# bierkasten.net
KiCad netlist of a schematic drawn in EAGLE
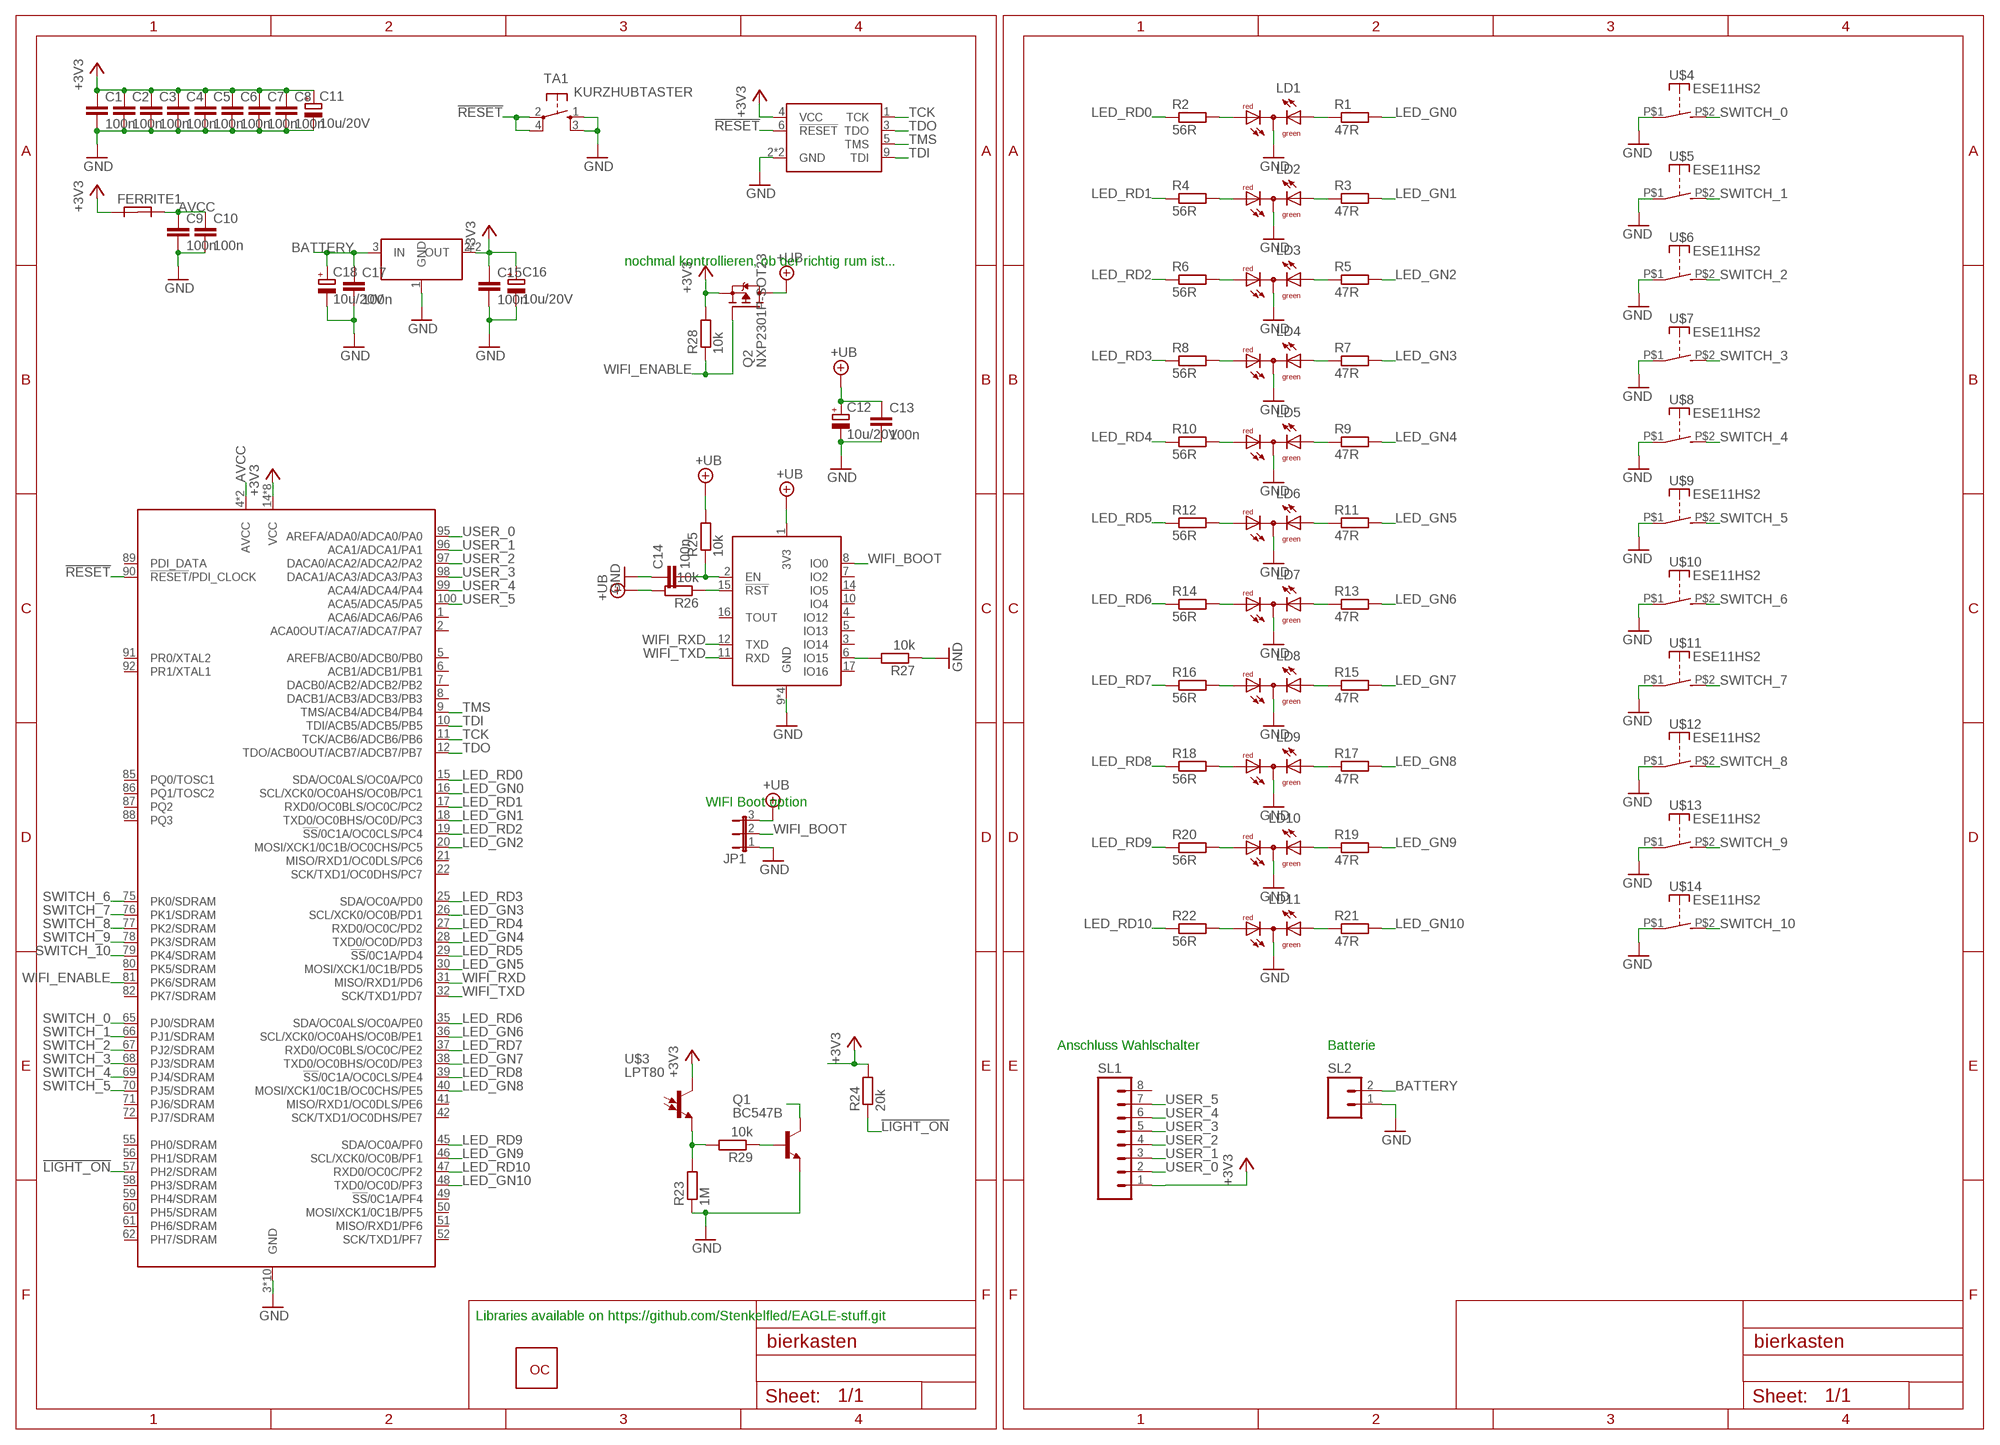
[diagram p0: schematic, sheet 1]

(export (version "E")
  (design (tool "Eeschema 10.0.6"))
  (components
    (comp (ref "C1")
      (value "100n")
      (footprint "eagle-import:C0603")
      (libsource (lib "eagle-import") (part "C-EUC0603"))
    )
    (comp (ref "C2")
      (value "100n")
      (footprint "eagle-import:C0603")
      (libsource (lib "eagle-import") (part "C-EUC0603"))
    )
    (comp (ref "C3")
      (value "100n")
      (footprint "eagle-import:C0603")
      (libsource (lib "eagle-import") (part "C-EUC0603"))
    )
    (comp (ref "C4")
      (value "100n")
      (footprint "eagle-import:C0603")
      (libsource (lib "eagle-import") (part "C-EUC0603"))
    )
    (comp (ref "C5")
      (value "100n")
      (footprint "eagle-import:C0603")
      (libsource (lib "eagle-import") (part "C-EUC0603"))
    )
    (comp (ref "C6")
      (value "100n")
      (footprint "eagle-import:C0603")
      (libsource (lib "eagle-import") (part "C-EUC0603"))
    )
    (comp (ref "C7")
      (value "100n")
      (footprint "eagle-import:C0603")
      (libsource (lib "eagle-import") (part "C-EUC0603"))
    )
    (comp (ref "C8")
      (value "100n")
      (footprint "eagle-import:C0603")
      (libsource (lib "eagle-import") (part "C-EUC0603"))
    )
    (comp (ref "C9")
      (value "100n")
      (footprint "eagle-import:C0603")
      (libsource (lib "eagle-import") (part "C-EUC0603"))
    )
    (comp (ref "C10")
      (value "100n")
      (footprint "eagle-import:C0603")
      (libsource (lib "eagle-import") (part "C-EUC0603"))
    )
    (comp (ref "C11")
      (value "10u/20V")
      (footprint "eagle-import:B_3528-21W")
      (libsource (lib "eagle-import") (part "CPOL-EUB/3528-21W"))
    )
    (comp (ref "C12")
      (value "10u/20V")
      (footprint "eagle-import:B_3528-21W")
      (libsource (lib "eagle-import") (part "CPOL-EUB/3528-21W"))
    )
    (comp (ref "C13")
      (value "100n")
      (footprint "eagle-import:C0603")
      (libsource (lib "eagle-import") (part "C-EUC0603"))
    )
    (comp (ref "C14")
      (value "100n")
      (footprint "eagle-import:C0603")
      (libsource (lib "eagle-import") (part "C-EUC0603"))
    )
    (comp (ref "C15")
      (value "100n")
      (footprint "eagle-import:C0603")
      (libsource (lib "eagle-import") (part "C-EUC0603"))
    )
    (comp (ref "C16")
      (value "10u/20V")
      (footprint "eagle-import:B_3528-21W")
      (libsource (lib "eagle-import") (part "CPOL-EUB/3528-21W"))
    )
    (comp (ref "C17")
      (value "100n")
      (footprint "eagle-import:C0603")
      (libsource (lib "eagle-import") (part "C-EUC0603"))
    )
    (comp (ref "C18")
      (value "10u/20V")
      (footprint "eagle-import:B_3528-21W")
      (libsource (lib "eagle-import") (part "CPOL-EUB/3528-21W"))
    )
    (comp (ref "FERRITE1")
      (value "FERRITE-EU_0805")
      (footprint "eagle-import:L0805")
      (libsource (lib "eagle-import") (part "FERRITE-EU_0805"))
    )
    (comp (ref "JP1")
      (value "JP2E")
      (footprint "eagle-import:JP2")
      (libsource (lib "eagle-import") (part "JP2E"))
    )
    (comp (ref "LD1")
      (value "DUOLED-RG-C-WIRE")
      (footprint "eagle-import:DUOLED-C-WIRE")
      (libsource (lib "eagle-import") (part "DUOLED-RG-C-WIRE"))
    )
    (comp (ref "LD2")
      (value "DUOLED-RG-C-WIRE")
      (footprint "eagle-import:DUOLED-C-WIRE")
      (libsource (lib "eagle-import") (part "DUOLED-RG-C-WIRE"))
    )
    (comp (ref "LD3")
      (value "DUOLED-RG-C-WIRE")
      (footprint "eagle-import:DUOLED-C-WIRE")
      (libsource (lib "eagle-import") (part "DUOLED-RG-C-WIRE"))
    )
    (comp (ref "LD4")
      (value "DUOLED-RG-C-WIRE")
      (footprint "eagle-import:DUOLED-C-WIRE")
      (libsource (lib "eagle-import") (part "DUOLED-RG-C-WIRE"))
    )
    (comp (ref "LD5")
      (value "DUOLED-RG-C-WIRE")
      (footprint "eagle-import:DUOLED-C-WIRE")
      (libsource (lib "eagle-import") (part "DUOLED-RG-C-WIRE"))
    )
    (comp (ref "LD6")
      (value "DUOLED-RG-C-WIRE")
      (footprint "eagle-import:DUOLED-C-WIRE")
      (libsource (lib "eagle-import") (part "DUOLED-RG-C-WIRE"))
    )
    (comp (ref "LD7")
      (value "DUOLED-RG-C-WIRE")
      (footprint "eagle-import:DUOLED-C-WIRE")
      (libsource (lib "eagle-import") (part "DUOLED-RG-C-WIRE"))
    )
    (comp (ref "LD8")
      (value "DUOLED-RG-C-WIRE")
      (footprint "eagle-import:DUOLED-C-WIRE")
      (libsource (lib "eagle-import") (part "DUOLED-RG-C-WIRE"))
    )
    (comp (ref "LD9")
      (value "DUOLED-RG-C-WIRE")
      (footprint "eagle-import:DUOLED-C-WIRE")
      (libsource (lib "eagle-import") (part "DUOLED-RG-C-WIRE"))
    )
    (comp (ref "LD10")
      (value "DUOLED-RG-C-WIRE")
      (footprint "eagle-import:DUOLED-C-WIRE")
      (libsource (lib "eagle-import") (part "DUOLED-RG-C-WIRE"))
    )
    (comp (ref "LD11")
      (value "DUOLED-RG-C-WIRE")
      (footprint "eagle-import:DUOLED-C-WIRE")
      (libsource (lib "eagle-import") (part "DUOLED-RG-C-WIRE"))
    )
    (comp (ref "Q1")
      (value "BC547B")
      (footprint "eagle-import:TO92")
      (libsource (lib "eagle-import") (part "BC547B"))
    )
    (comp (ref "Q2")
      (value "NXP2301P-SOT23")
      (footprint "eagle-import:SOT23")
      (libsource (lib "eagle-import") (part "NXP2301P-SOT23"))
    )
    (comp (ref "R1")
      (value "47R")
      (footprint "eagle-import:R0603")
      (libsource (lib "eagle-import") (part "rcl_STE_R-EU_R0603"))
    )
    (comp (ref "R2")
      (value "56R")
      (footprint "eagle-import:R0603")
      (libsource (lib "eagle-import") (part "rcl_STE_R-EU_R0603"))
    )
    (comp (ref "R3")
      (value "47R")
      (footprint "eagle-import:R0603")
      (libsource (lib "eagle-import") (part "rcl_STE_R-EU_R0603"))
    )
    (comp (ref "R4")
      (value "56R")
      (footprint "eagle-import:R0603")
      (libsource (lib "eagle-import") (part "rcl_STE_R-EU_R0603"))
    )
    (comp (ref "R5")
      (value "47R")
      (footprint "eagle-import:R0603")
      (libsource (lib "eagle-import") (part "rcl_STE_R-EU_R0603"))
    )
    (comp (ref "R6")
      (value "56R")
      (footprint "eagle-import:R0603")
      (libsource (lib "eagle-import") (part "rcl_STE_R-EU_R0603"))
    )
    (comp (ref "R7")
      (value "47R")
      (footprint "eagle-import:R0603")
      (libsource (lib "eagle-import") (part "rcl_STE_R-EU_R0603"))
    )
    (comp (ref "R8")
      (value "56R")
      (footprint "eagle-import:R0603")
      (libsource (lib "eagle-import") (part "rcl_STE_R-EU_R0603"))
    )
    (comp (ref "R9")
      (value "47R")
      (footprint "eagle-import:R0603")
      (libsource (lib "eagle-import") (part "rcl_STE_R-EU_R0603"))
    )
    (comp (ref "R10")
      (value "56R")
      (footprint "eagle-import:R0603")
      (libsource (lib "eagle-import") (part "rcl_STE_R-EU_R0603"))
    )
    (comp (ref "R11")
      (value "47R")
      (footprint "eagle-import:R0603")
      (libsource (lib "eagle-import") (part "rcl_STE_R-EU_R0603"))
    )
    (comp (ref "R12")
      (value "56R")
      (footprint "eagle-import:R0603")
      (libsource (lib "eagle-import") (part "rcl_STE_R-EU_R0603"))
    )
    (comp (ref "R13")
      (value "47R")
      (footprint "eagle-import:R0603")
      (libsource (lib "eagle-import") (part "rcl_STE_R-EU_R0603"))
    )
    (comp (ref "R14")
      (value "56R")
      (footprint "eagle-import:R0603")
      (libsource (lib "eagle-import") (part "rcl_STE_R-EU_R0603"))
    )
    (comp (ref "R15")
      (value "47R")
      (footprint "eagle-import:R0603")
      (libsource (lib "eagle-import") (part "R-EU_R0603"))
    )
    (comp (ref "R16")
      (value "56R")
      (footprint "eagle-import:R0603")
      (libsource (lib "eagle-import") (part "rcl_STE_R-EU_R0603"))
    )
    (comp (ref "R17")
      (value "47R")
      (footprint "eagle-import:R0603")
      (libsource (lib "eagle-import") (part "rcl_STE_R-EU_R0603"))
    )
    (comp (ref "R18")
      (value "56R")
      (footprint "eagle-import:R0603")
      (libsource (lib "eagle-import") (part "rcl_STE_R-EU_R0603"))
    )
    (comp (ref "R19")
      (value "47R")
      (footprint "eagle-import:R0603")
      (libsource (lib "eagle-import") (part "rcl_STE_R-EU_R0603"))
    )
    (comp (ref "R20")
      (value "56R")
      (footprint "eagle-import:R0603")
      (libsource (lib "eagle-import") (part "rcl_STE_R-EU_R0603"))
    )
    (comp (ref "R21")
      (value "47R")
      (footprint "eagle-import:R0603")
      (libsource (lib "eagle-import") (part "rcl_STE_R-EU_R0603"))
    )
    (comp (ref "R22")
      (value "56R")
      (footprint "eagle-import:R0603")
      (libsource (lib "eagle-import") (part "rcl_STE_R-EU_R0603"))
    )
    (comp (ref "R23")
      (value "1M")
      (footprint "eagle-import:R0603")
      (libsource (lib "eagle-import") (part "rcl_STE_R-EU_R0603"))
    )
    (comp (ref "R24")
      (value "20k")
      (footprint "eagle-import:R0603")
      (libsource (lib "eagle-import") (part "rcl_STE_R-EU_R0603"))
    )
    (comp (ref "R25")
      (value "10k")
      (footprint "eagle-import:R0603")
      (libsource (lib "eagle-import") (part "R-EU_R0603"))
    )
    (comp (ref "R26")
      (value "10k")
      (footprint "eagle-import:R0603")
      (libsource (lib "eagle-import") (part "R-EU_R0603"))
    )
    (comp (ref "R27")
      (value "10k")
      (footprint "eagle-import:R0603")
      (libsource (lib "eagle-import") (part "R-EU_R0603"))
    )
    (comp (ref "R28")
      (value "10k")
      (footprint "eagle-import:R0603")
      (libsource (lib "eagle-import") (part "R-EU_R0603"))
    )
    (comp (ref "R29")
      (value "10k")
      (footprint "eagle-import:R0603")
      (libsource (lib "eagle-import") (part "rcl_STE_R-EU_R0603"))
    )
    (comp (ref "SL1")
      (value "M08")
      (footprint "eagle-import:08P")
      (libsource (lib "eagle-import") (part "M08"))
    )
    (comp (ref "SL2")
      (value "M02")
      (footprint "eagle-import:02P")
      (libsource (lib "eagle-import") (part "M02"))
    )
    (comp (ref "TA1")
      (value "KURZHUBTASTER")
      (footprint "eagle-import:TA93XX")
      (libsource (lib "eagle-import") (part "KURZHUBTASTER"))
    )
    (comp (ref "U$1")
      (value "ATXMEGA_A1")
      (footprint "eagle-import:TQFP100")
      (libsource (lib "eagle-import") (part "ATXMEGA_A1"))
    )
    (comp (ref "U$2")
      (value "AVR-JTAG-10")
      (footprint "eagle-import:WANNE10G")
      (libsource (lib "eagle-import") (part "AVR-JTAG-10"))
    )
    (comp (ref "U$3")
      (value "LPT80")
      (footprint "eagle-import:LPT80")
      (libsource (lib "eagle-import") (part "LPT80"))
    )
    (comp (ref "U$4")
      (value "ESE11HS2")
      (footprint "eagle-import:2X2,54")
      (libsource (lib "eagle-import") (part "SWITCH_SINGLE-WIRED"))
    )
    (comp (ref "U$5")
      (value "ESE11HS2")
      (footprint "eagle-import:2X2,54")
      (libsource (lib "eagle-import") (part "SWITCH_SINGLE-WIRED"))
    )
    (comp (ref "U$6")
      (value "ESE11HS2")
      (footprint "eagle-import:2X2,54")
      (libsource (lib "eagle-import") (part "SWITCH_SINGLE-WIRED"))
    )
    (comp (ref "U$7")
      (value "ESE11HS2")
      (footprint "eagle-import:2X2,54")
      (libsource (lib "eagle-import") (part "SWITCH_SINGLE-WIRED"))
    )
    (comp (ref "U$8")
      (value "ESE11HS2")
      (footprint "eagle-import:2X2,54")
      (libsource (lib "eagle-import") (part "SWITCH_SINGLE-WIRED"))
    )
    (comp (ref "U$9")
      (value "ESE11HS2")
      (footprint "eagle-import:2X2,54")
      (libsource (lib "eagle-import") (part "SWITCH_SINGLE-WIRED"))
    )
    (comp (ref "U$10")
      (value "ESE11HS2")
      (footprint "eagle-import:2X2,54")
      (libsource (lib "eagle-import") (part "SWITCH_SINGLE-WIRED"))
    )
    (comp (ref "U$11")
      (value "ESE11HS2")
      (footprint "eagle-import:2X2,54")
      (libsource (lib "eagle-import") (part "SWITCH_SINGLE-WIRED"))
    )
    (comp (ref "U$12")
      (value "ESE11HS2")
      (footprint "eagle-import:2X2,54")
      (libsource (lib "eagle-import") (part "SWITCH_SINGLE-WIRED"))
    )
    (comp (ref "U$13")
      (value "ESE11HS2")
      (footprint "eagle-import:2X2,54")
      (libsource (lib "eagle-import") (part "SWITCH_SINGLE-WIRED"))
    )
    (comp (ref "U$14")
      (value "ESE11HS2")
      (footprint "eagle-import:2X2,54")
      (libsource (lib "eagle-import") (part "SWITCH_SINGLE-WIRED"))
    )
    (comp (ref "U$15")
      (value "ESP8266-POLLIN")
      (footprint "eagle-import:ESP8266-POLLIN")
      (libsource (lib "eagle-import") (part "ESP8266-POLLIN"))
    )
    (comp (ref "U$16")
      (value "NCP1117ST33T3G")
      (footprint "eagle-import:SOT223")
      (libsource (lib "eagle-import") (part "NCP1117ST33"))
    )
    (comp (ref "U$17")
      (value "BESTELLTEILE")
      (footprint "eagle-import:BESTELLTEILE")
      (libsource (lib "eagle-import") (part "BESTELLTEILE"))
    )
  )
  (nets
    (net (code "1") (name "+3V3") (class "Default")
      (node (ref "C1") (pin "1") (pinfunction "1_1") (pintype "passive"))
      (node (ref "C11") (pin "+") (pinfunction "+_+") (pintype "passive"))
      (node (ref "C15") (pin "1") (pinfunction "1_1") (pintype "passive"))
      (node (ref "C16") (pin "+") (pinfunction "+_+") (pintype "passive"))
      (node (ref "C2") (pin "1") (pinfunction "1_1") (pintype "passive"))
      (node (ref "C3") (pin "1") (pinfunction "1_1") (pintype "passive"))
      (node (ref "C4") (pin "1") (pinfunction "1_1") (pintype "passive"))
      (node (ref "C5") (pin "1") (pinfunction "1_1") (pintype "passive"))
      (node (ref "C6") (pin "1") (pinfunction "1_1") (pintype "passive"))
      (node (ref "C7") (pin "1") (pinfunction "1_1") (pintype "passive"))
      (node (ref "C8") (pin "1") (pinfunction "1_1") (pintype "passive"))
      (node (ref "FERRITE1") (pin "1") (pinfunction "1_1") (pintype "passive"))
      (node (ref "Q2") (pin "2") (pinfunction "S_2") (pintype "passive"))
      (node (ref "R24") (pin "2") (pinfunction "2_2") (pintype "passive"))
      (node (ref "R28") (pin "2") (pinfunction "2_2") (pintype "passive"))
      (node (ref "SL1") (pin "1") (pinfunction "1_1") (pintype "passive"))
      (node (ref "U$1") (pin "14") (pinfunction "VCC_14") (pintype "power_in"))
      (node (ref "U$1") (pin "24") (pinfunction "VCC_24") (pintype "power_in"))
      (node (ref "U$1") (pin "34") (pinfunction "VCC_34") (pintype "power_in"))
      (node (ref "U$1") (pin "44") (pinfunction "VCC_44") (pintype "power_in"))
      (node (ref "U$1") (pin "54") (pinfunction "VCC_54") (pintype "power_in"))
      (node (ref "U$1") (pin "64") (pinfunction "VCC_64") (pintype "power_in"))
      (node (ref "U$1") (pin "74") (pinfunction "VCC_74") (pintype "power_in"))
      (node (ref "U$1") (pin "83") (pinfunction "VCC_83") (pintype "power_in"))
      (node (ref "U$16") (pin "2") (pinfunction "OUT_2") (pintype "power_in"))
      (node (ref "U$16") (pin "4") (pinfunction "OUT_4") (pintype "power_in"))
      (node (ref "U$2") (pin "4") (pinfunction "VCC_4") (pintype "power_in"))
      (node (ref "U$3") (pin "C") (pinfunction "C_C") (pintype "passive"))
    )
    (net (code "2") (name "+UB") (class "Default")
      (node (ref "C12") (pin "+") (pinfunction "+_+") (pintype "passive"))
      (node (ref "C13") (pin "1") (pinfunction "1_1") (pintype "passive"))
      (node (ref "JP1") (pin "3") (pinfunction "3_3") (pintype "passive"))
      (node (ref "Q2") (pin "3") (pinfunction "D_3") (pintype "passive"))
      (node (ref "R25") (pin "2") (pinfunction "2_2") (pintype "passive"))
      (node (ref "R26") (pin "2") (pinfunction "2_2") (pintype "passive"))
      (node (ref "U$15") (pin "1") (pinfunction "3V3_1") (pintype "power_in"))
    )
    (net (code "3") (name "/AVCC") (class "Default")
      (node (ref "C10") (pin "1") (pinfunction "1_1") (pintype "passive"))
      (node (ref "C9") (pin "1") (pinfunction "1_1") (pintype "passive"))
      (node (ref "FERRITE1") (pin "2") (pinfunction "2_2") (pintype "passive"))
      (node (ref "U$1") (pin "4") (pinfunction "AVCC_4") (pintype "power_in"))
      (node (ref "U$1") (pin "94") (pinfunction "AVCC_94") (pintype "power_in"))
    )
    (net (code "4") (name "/BATTERY") (class "Default")
      (node (ref "C17") (pin "1") (pinfunction "1_1") (pintype "passive"))
      (node (ref "C18") (pin "+") (pinfunction "+_+") (pintype "passive"))
      (node (ref "SL2") (pin "2") (pinfunction "2_2") (pintype "passive"))
      (node (ref "U$16") (pin "3") (pinfunction "IN_3") (pintype "power_in"))
    )
    (net (code "5") (name "/LED_GN0") (class "Default")
      (node (ref "R1") (pin "2") (pinfunction "2_2") (pintype "passive"))
      (node (ref "U$1") (pin "16") (pinfunction "SCL/XCK0/OC0AHS/OC0B/PC1_16") (pintype "bidirectional"))
    )
    (net (code "6") (name "/LED_GN1") (class "Default")
      (node (ref "R3") (pin "2") (pinfunction "2_2") (pintype "passive"))
      (node (ref "U$1") (pin "18") (pinfunction "TXD0/OC0BHS/OC0D/PC3_18") (pintype "bidirectional"))
    )
    (net (code "7") (name "/LED_GN2") (class "Default")
      (node (ref "R5") (pin "2") (pinfunction "2_2") (pintype "passive"))
      (node (ref "U$1") (pin "20") (pinfunction "MOSI/XCK1/0C1B/OC0CHS/PC5_20") (pintype "bidirectional"))
    )
    (net (code "8") (name "/LED_GN3") (class "Default")
      (node (ref "R7") (pin "2") (pinfunction "2_2") (pintype "passive"))
      (node (ref "U$1") (pin "26") (pinfunction "SCL/XCK0/OC0B/PD1_26") (pintype "bidirectional"))
    )
    (net (code "9") (name "/LED_GN4") (class "Default")
      (node (ref "R9") (pin "2") (pinfunction "2_2") (pintype "passive"))
      (node (ref "U$1") (pin "28") (pinfunction "TXD0/OC0D/PD3_28") (pintype "bidirectional"))
    )
    (net (code "10") (name "/LED_GN5") (class "Default")
      (node (ref "R11") (pin "2") (pinfunction "2_2") (pintype "passive"))
      (node (ref "U$1") (pin "30") (pinfunction "MOSI/XCK1/0C1B/PD5_30") (pintype "bidirectional"))
    )
    (net (code "11") (name "/LED_GN6") (class "Default")
      (node (ref "R13") (pin "2") (pinfunction "2_2") (pintype "passive"))
      (node (ref "U$1") (pin "36") (pinfunction "SCL/XCK0/OC0AHS/OC0B/PE1_36") (pintype "bidirectional"))
    )
    (net (code "12") (name "/LED_GN7") (class "Default")
      (node (ref "R15") (pin "2") (pinfunction "2_2") (pintype "passive"))
      (node (ref "U$1") (pin "38") (pinfunction "TXD0/OC0BHS/OC0D/PE3_38") (pintype "bidirectional"))
    )
    (net (code "13") (name "/LED_GN8") (class "Default")
      (node (ref "R17") (pin "2") (pinfunction "2_2") (pintype "passive"))
      (node (ref "U$1") (pin "40") (pinfunction "MOSI/XCK1/0C1B/OC0CHS/PE5_40") (pintype "bidirectional"))
    )
    (net (code "14") (name "/LED_GN9") (class "Default")
      (node (ref "R19") (pin "2") (pinfunction "2_2") (pintype "passive"))
      (node (ref "U$1") (pin "46") (pinfunction "SCL/XCK0/OC0B/PF1_46") (pintype "bidirectional"))
    )
    (net (code "15") (name "/LED_GN10") (class "Default")
      (node (ref "R21") (pin "2") (pinfunction "2_2") (pintype "passive"))
      (node (ref "U$1") (pin "48") (pinfunction "TXD0/OC0D/PF3_48") (pintype "bidirectional"))
    )
    (net (code "16") (name "/LED_RD0") (class "Default")
      (node (ref "R2") (pin "1") (pinfunction "1_1") (pintype "passive"))
      (node (ref "U$1") (pin "15") (pinfunction "SDA/OC0ALS/OC0A/PC0_15") (pintype "bidirectional"))
    )
    (net (code "17") (name "/LED_RD1") (class "Default")
      (node (ref "R4") (pin "1") (pinfunction "1_1") (pintype "passive"))
      (node (ref "U$1") (pin "17") (pinfunction "RXD0/OC0BLS/OC0C/PC2_17") (pintype "bidirectional"))
    )
    (net (code "18") (name "/LED_RD2") (class "Default")
      (node (ref "R6") (pin "1") (pinfunction "1_1") (pintype "passive"))
      (node (ref "U$1") (pin "19") (pinfunction "~{SS}/0C1A/OC0CLS/PC4_19") (pintype "bidirectional"))
    )
    (net (code "19") (name "/LED_RD3") (class "Default")
      (node (ref "R8") (pin "1") (pinfunction "1_1") (pintype "passive"))
      (node (ref "U$1") (pin "25") (pinfunction "SDA/OC0A/PD0_25") (pintype "bidirectional"))
    )
    (net (code "20") (name "/LED_RD4") (class "Default")
      (node (ref "R10") (pin "1") (pinfunction "1_1") (pintype "passive"))
      (node (ref "U$1") (pin "27") (pinfunction "RXD0/OC0C/PD2_27") (pintype "bidirectional"))
    )
    (net (code "21") (name "/LED_RD5") (class "Default")
      (node (ref "R12") (pin "1") (pinfunction "1_1") (pintype "passive"))
      (node (ref "U$1") (pin "29") (pinfunction "~{SS}/0C1A/PD4_29") (pintype "bidirectional"))
    )
    (net (code "22") (name "/LED_RD6") (class "Default")
      (node (ref "R14") (pin "1") (pinfunction "1_1") (pintype "passive"))
      (node (ref "U$1") (pin "35") (pinfunction "SDA/OC0ALS/OC0A/PE0_35") (pintype "bidirectional"))
    )
    (net (code "23") (name "/LED_RD7") (class "Default")
      (node (ref "R16") (pin "1") (pinfunction "1_1") (pintype "passive"))
      (node (ref "U$1") (pin "37") (pinfunction "RXD0/OC0BLS/OC0C/PE2_37") (pintype "bidirectional"))
    )
    (net (code "24") (name "/LED_RD8") (class "Default")
      (node (ref "R18") (pin "1") (pinfunction "1_1") (pintype "passive"))
      (node (ref "U$1") (pin "39") (pinfunction "~{SS}/0C1A/OC0CLS/PE4_39") (pintype "bidirectional"))
    )
    (net (code "25") (name "/LED_RD9") (class "Default")
      (node (ref "R20") (pin "1") (pinfunction "1_1") (pintype "passive"))
      (node (ref "U$1") (pin "45") (pinfunction "SDA/OC0A/PF0_45") (pintype "bidirectional"))
    )
    (net (code "26") (name "/LED_RD10") (class "Default")
      (node (ref "R22") (pin "1") (pinfunction "1_1") (pintype "passive"))
      (node (ref "U$1") (pin "47") (pinfunction "RXD0/OC0C/PF2_47") (pintype "bidirectional"))
    )
    (net (code "27") (name "/SWITCH_0") (class "Default")
      (node (ref "U$1") (pin "65") (pinfunction "PJ0/SDRAM_65") (pintype "bidirectional"))
      (node (ref "U$4") (pin "P$2") (pinfunction "S_P$2") (pintype "passive"))
    )
    (net (code "28") (name "/SWITCH_1") (class "Default")
      (node (ref "U$1") (pin "66") (pinfunction "PJ1/SDRAM_66") (pintype "bidirectional"))
      (node (ref "U$5") (pin "P$2") (pinfunction "S_P$2") (pintype "passive"))
    )
    (net (code "29") (name "/SWITCH_2") (class "Default")
      (node (ref "U$1") (pin "67") (pinfunction "PJ2/SDRAM_67") (pintype "bidirectional"))
      (node (ref "U$6") (pin "P$2") (pinfunction "S_P$2") (pintype "passive"))
    )
    (net (code "30") (name "/SWITCH_3") (class "Default")
      (node (ref "U$1") (pin "68") (pinfunction "PJ3/SDRAM_68") (pintype "bidirectional"))
      (node (ref "U$7") (pin "P$2") (pinfunction "S_P$2") (pintype "passive"))
    )
    (net (code "31") (name "/SWITCH_4") (class "Default")
      (node (ref "U$1") (pin "69") (pinfunction "PJ4/SDRAM_69") (pintype "bidirectional"))
      (node (ref "U$8") (pin "P$2") (pinfunction "S_P$2") (pintype "passive"))
    )
    (net (code "32") (name "/SWITCH_5") (class "Default")
      (node (ref "U$1") (pin "70") (pinfunction "PJ5/SDRAM_70") (pintype "bidirectional"))
      (node (ref "U$9") (pin "P$2") (pinfunction "S_P$2") (pintype "passive"))
    )
    (net (code "33") (name "/SWITCH_6") (class "Default")
      (node (ref "U$1") (pin "75") (pinfunction "PK0/SDRAM_75") (pintype "bidirectional"))
      (node (ref "U$10") (pin "P$2") (pinfunction "S_P$2") (pintype "passive"))
    )
    (net (code "34") (name "/SWITCH_7") (class "Default")
      (node (ref "U$1") (pin "76") (pinfunction "PK1/SDRAM_76") (pintype "bidirectional"))
      (node (ref "U$11") (pin "P$2") (pinfunction "S_P$2") (pintype "passive"))
    )
    (net (code "35") (name "/SWITCH_8") (class "Default")
      (node (ref "U$1") (pin "77") (pinfunction "PK2/SDRAM_77") (pintype "bidirectional"))
      (node (ref "U$12") (pin "P$2") (pinfunction "S_P$2") (pintype "passive"))
    )
    (net (code "36") (name "/SWITCH_9") (class "Default")
      (node (ref "U$1") (pin "78") (pinfunction "PK3/SDRAM_78") (pintype "bidirectional"))
      (node (ref "U$13") (pin "P$2") (pinfunction "S_P$2") (pintype "passive"))
    )
    (net (code "37") (name "/SWITCH_10") (class "Default")
      (node (ref "U$1") (pin "79") (pinfunction "PK4/SDRAM_79") (pintype "bidirectional"))
      (node (ref "U$14") (pin "P$2") (pinfunction "S_P$2") (pintype "passive"))
    )
    (net (code "38") (name "/TCK") (class "Default")
      (node (ref "U$1") (pin "11") (pinfunction "TCK/ACB6/ADCB6/PB6_11") (pintype "bidirectional"))
      (node (ref "U$2") (pin "1") (pinfunction "TCK_1") (pintype "bidirectional"))
    )
    (net (code "39") (name "/TDI") (class "Default")
      (node (ref "U$1") (pin "10") (pinfunction "TDI/ACB5/ADCB5/PB5_10") (pintype "bidirectional"))
      (node (ref "U$2") (pin "9") (pinfunction "TDI_9") (pintype "bidirectional"))
    )
    (net (code "40") (name "/TDO") (class "Default")
      (node (ref "U$1") (pin "12") (pinfunction "TDO/ACB0OUT/ACB7/ADCB7/PB7_12") (pintype "bidirectional"))
      (node (ref "U$2") (pin "3") (pinfunction "TDO_3") (pintype "bidirectional"))
    )
    (net (code "41") (name "/TMS") (class "Default")
      (node (ref "U$1") (pin "9") (pinfunction "TMS/ACB4/ADCB4/PB4_9") (pintype "bidirectional"))
      (node (ref "U$2") (pin "5") (pinfunction "TMS_5") (pintype "bidirectional"))
    )
    (net (code "42") (name "/USER_0") (class "Default")
      (node (ref "SL1") (pin "2") (pinfunction "2_2") (pintype "passive"))
      (node (ref "U$1") (pin "95") (pinfunction "AREFA/ADA0/ADCA0/PA0_95") (pintype "bidirectional"))
    )
    (net (code "43") (name "/USER_1") (class "Default")
      (node (ref "SL1") (pin "3") (pinfunction "3_3") (pintype "passive"))
      (node (ref "U$1") (pin "96") (pinfunction "ACA1/ADCA1/PA1_96") (pintype "bidirectional"))
    )
    (net (code "44") (name "/USER_2") (class "Default")
      (node (ref "SL1") (pin "4") (pinfunction "4_4") (pintype "passive"))
      (node (ref "U$1") (pin "97") (pinfunction "DACA0/ACA2/ADCA2/PA2_97") (pintype "bidirectional"))
    )
    (net (code "45") (name "/USER_3") (class "Default")
      (node (ref "SL1") (pin "5") (pinfunction "5_5") (pintype "passive"))
      (node (ref "U$1") (pin "98") (pinfunction "DACA1/ACA3/ADCA3/PA3_98") (pintype "bidirectional"))
    )
    (net (code "46") (name "/USER_4") (class "Default")
      (node (ref "SL1") (pin "6") (pinfunction "6_6") (pintype "passive"))
      (node (ref "U$1") (pin "99") (pinfunction "ACA4/ADCA4/PA4_99") (pintype "bidirectional"))
    )
    (net (code "47") (name "/USER_5") (class "Default")
      (node (ref "SL1") (pin "7") (pinfunction "7_7") (pintype "passive"))
      (node (ref "U$1") (pin "100") (pinfunction "ACA5/ADCA5/PA5_100") (pintype "bidirectional"))
    )
    (net (code "48") (name "/WIFI_BOOT") (class "Default")
      (node (ref "JP1") (pin "2") (pinfunction "2_2") (pintype "passive"))
      (node (ref "U$15") (pin "8") (pinfunction "IO0_8") (pintype "bidirectional"))
    )
    (net (code "49") (name "/WIFI_ENABLE") (class "Default")
      (node (ref "Q2") (pin "1") (pinfunction "G_1") (pintype "passive"))
      (node (ref "R28") (pin "1") (pinfunction "1_1") (pintype "passive"))
      (node (ref "U$1") (pin "81") (pinfunction "PK6/SDRAM_81") (pintype "bidirectional"))
    )
    (net (code "50") (name "/WIFI_RXD") (class "Default")
      (node (ref "U$1") (pin "31") (pinfunction "MISO/RXD1/PD6_31") (pintype "bidirectional"))
      (node (ref "U$15") (pin "12") (pinfunction "TXD_12") (pintype "bidirectional"))
    )
    (net (code "51") (name "/WIFI_TXD") (class "Default")
      (node (ref "U$1") (pin "32") (pinfunction "SCK/TXD1/PD7_32") (pintype "bidirectional"))
      (node (ref "U$15") (pin "11") (pinfunction "RXD_11") (pintype "bidirectional"))
    )
    (net (code "52") (name "/~{LIGHT_ON}") (class "Default")
      (node (ref "R24") (pin "1") (pinfunction "1_1") (pintype "passive"))
      (node (ref "U$1") (pin "57") (pinfunction "PH2/SDRAM_57") (pintype "bidirectional"))
    )
    (net (code "53") (name "/~{RESET}") (class "Default")
      (node (ref "TA1") (pin "2") (pinfunction "P_2") (pintype "passive"))
      (node (ref "TA1") (pin "4") (pinfunction "P1_4") (pintype "passive"))
      (node (ref "U$1") (pin "90") (pinfunction "~{RESET}/PDI_CLOCK_90") (pintype "bidirectional"))
      (node (ref "U$2") (pin "6") (pinfunction "~{RESET}_6") (pintype "bidirectional"))
    )
    (net (code "54") (name "GND") (class "Default")
      (node (ref "C1") (pin "2") (pinfunction "2_2") (pintype "passive"))
      (node (ref "C10") (pin "2") (pinfunction "2_2") (pintype "passive"))
      (node (ref "C11") (pin "-") (pinfunction "-_-") (pintype "passive"))
      (node (ref "C12") (pin "-") (pinfunction "-_-") (pintype "passive"))
      (node (ref "C13") (pin "2") (pinfunction "2_2") (pintype "passive"))
      (node (ref "C14") (pin "1") (pinfunction "1_1") (pintype "passive"))
      (node (ref "C15") (pin "2") (pinfunction "2_2") (pintype "passive"))
      (node (ref "C16") (pin "-") (pinfunction "-_-") (pintype "passive"))
      (node (ref "C17") (pin "2") (pinfunction "2_2") (pintype "passive"))
      (node (ref "C18") (pin "-") (pinfunction "-_-") (pintype "passive"))
      (node (ref "C2") (pin "2") (pinfunction "2_2") (pintype "passive"))
      (node (ref "C3") (pin "2") (pinfunction "2_2") (pintype "passive"))
      (node (ref "C4") (pin "2") (pinfunction "2_2") (pintype "passive"))
      (node (ref "C5") (pin "2") (pinfunction "2_2") (pintype "passive"))
      (node (ref "C6") (pin "2") (pinfunction "2_2") (pintype "passive"))
      (node (ref "C7") (pin "2") (pinfunction "2_2") (pintype "passive"))
      (node (ref "C8") (pin "2") (pinfunction "2_2") (pintype "passive"))
      (node (ref "C9") (pin "2") (pinfunction "2_2") (pintype "passive"))
      (node (ref "JP1") (pin "1") (pinfunction "1_1") (pintype "passive"))
      (node (ref "LD1") (pin "C") (pinfunction "C_C") (pintype "passive"))
      (node (ref "LD10") (pin "C") (pinfunction "C_C") (pintype "passive"))
      (node (ref "LD11") (pin "C") (pinfunction "C_C") (pintype "passive"))
      (node (ref "LD2") (pin "C") (pinfunction "C_C") (pintype "passive"))
      (node (ref "LD3") (pin "C") (pinfunction "C_C") (pintype "passive"))
      (node (ref "LD4") (pin "C") (pinfunction "C_C") (pintype "passive"))
      (node (ref "LD5") (pin "C") (pinfunction "C_C") (pintype "passive"))
      (node (ref "LD6") (pin "C") (pinfunction "C_C") (pintype "passive"))
      (node (ref "LD7") (pin "C") (pinfunction "C_C") (pintype "passive"))
      (node (ref "LD8") (pin "C") (pinfunction "C_C") (pintype "passive"))
      (node (ref "LD9") (pin "C") (pinfunction "C_C") (pintype "passive"))
      (node (ref "Q1") (pin "1") (pinfunction "E_1") (pintype "passive"))
      (node (ref "R23") (pin "1") (pinfunction "1_1") (pintype "passive"))
      (node (ref "R27") (pin "1") (pinfunction "1_1") (pintype "passive"))
      (node (ref "SL2") (pin "1") (pinfunction "1_1") (pintype "passive"))
      (node (ref "TA1") (pin "1") (pinfunction "S_1") (pintype "passive"))
      (node (ref "TA1") (pin "3") (pinfunction "S1_3") (pintype "passive"))
      (node (ref "U$1") (pin "13") (pinfunction "GND_13") (pintype "power_in"))
      (node (ref "U$1") (pin "23") (pinfunction "GND_23") (pintype "power_in"))
      (node (ref "U$1") (pin "3") (pinfunction "GND_3") (pintype "power_in"))
      (node (ref "U$1") (pin "33") (pinfunction "GND_33") (pintype "power_in"))
      (node (ref "U$1") (pin "43") (pinfunction "GND_43") (pintype "power_in"))
      (node (ref "U$1") (pin "53") (pinfunction "GND_53") (pintype "power_in"))
      (node (ref "U$1") (pin "63") (pinfunction "GND_63") (pintype "power_in"))
      (node (ref "U$1") (pin "73") (pinfunction "GND_73") (pintype "power_in"))
      (node (ref "U$1") (pin "84") (pinfunction "GND_84") (pintype "power_in"))
      (node (ref "U$1") (pin "93") (pinfunction "GND_93") (pintype "power_in"))
      (node (ref "U$10") (pin "P$1") (pinfunction "P_P$1") (pintype "passive"))
      (node (ref "U$11") (pin "P$1") (pinfunction "P_P$1") (pintype "passive"))
      (node (ref "U$12") (pin "P$1") (pinfunction "P_P$1") (pintype "passive"))
      (node (ref "U$13") (pin "P$1") (pinfunction "P_P$1") (pintype "passive"))
      (node (ref "U$14") (pin "P$1") (pinfunction "P_P$1") (pintype "passive"))
      (node (ref "U$15") (pin "13") (pinfunction "GND_13") (pintype "power_in"))
      (node (ref "U$15") (pin "18") (pinfunction "GND_18") (pintype "power_in"))
      (node (ref "U$15") (pin "19") (pinfunction "GND_19") (pintype "power_in"))
      (node (ref "U$15") (pin "9") (pinfunction "GND_9") (pintype "power_in"))
      (node (ref "U$16") (pin "1") (pinfunction "GND_1") (pintype "power_in"))
      (node (ref "U$2") (pin "10") (pinfunction "GND_10") (pintype "power_in"))
      (node (ref "U$2") (pin "2") (pinfunction "GND_2") (pintype "power_in"))
      (node (ref "U$4") (pin "P$1") (pinfunction "P_P$1") (pintype "passive"))
      (node (ref "U$5") (pin "P$1") (pinfunction "P_P$1") (pintype "passive"))
      (node (ref "U$6") (pin "P$1") (pinfunction "P_P$1") (pintype "passive"))
      (node (ref "U$7") (pin "P$1") (pinfunction "P_P$1") (pintype "passive"))
      (node (ref "U$8") (pin "P$1") (pinfunction "P_P$1") (pintype "passive"))
      (node (ref "U$9") (pin "P$1") (pinfunction "P_P$1") (pintype "passive"))
    )
    (net (code "55") (name "Net-(LD1-AG)") (class "Default")
      (node (ref "LD1") (pin "AX") (pinfunction "AG_AX") (pintype "passive"))
      (node (ref "R1") (pin "1") (pinfunction "1_1") (pintype "passive"))
    )
    (net (code "56") (name "Net-(LD1-PadAR)") (class "Default")
      (node (ref "LD1") (pin "AR") (pinfunction "AR_AR") (pintype "passive"))
      (node (ref "R2") (pin "2") (pinfunction "2_2") (pintype "passive"))
    )
    (net (code "57") (name "Net-(LD2-AG)") (class "Default")
      (node (ref "LD2") (pin "AX") (pinfunction "AG_AX") (pintype "passive"))
      (node (ref "R3") (pin "1") (pinfunction "1_1") (pintype "passive"))
    )
    (net (code "58") (name "Net-(LD2-PadAR)") (class "Default")
      (node (ref "LD2") (pin "AR") (pinfunction "AR_AR") (pintype "passive"))
      (node (ref "R4") (pin "2") (pinfunction "2_2") (pintype "passive"))
    )
    (net (code "59") (name "Net-(LD3-AG)") (class "Default")
      (node (ref "LD3") (pin "AX") (pinfunction "AG_AX") (pintype "passive"))
      (node (ref "R5") (pin "1") (pinfunction "1_1") (pintype "passive"))
    )
    (net (code "60") (name "Net-(LD3-PadAR)") (class "Default")
      (node (ref "LD3") (pin "AR") (pinfunction "AR_AR") (pintype "passive"))
      (node (ref "R6") (pin "2") (pinfunction "2_2") (pintype "passive"))
    )
    (net (code "61") (name "Net-(LD4-AG)") (class "Default")
      (node (ref "LD4") (pin "AX") (pinfunction "AG_AX") (pintype "passive"))
      (node (ref "R7") (pin "1") (pinfunction "1_1") (pintype "passive"))
    )
    (net (code "62") (name "Net-(LD4-PadAR)") (class "Default")
      (node (ref "LD4") (pin "AR") (pinfunction "AR_AR") (pintype "passive"))
      (node (ref "R8") (pin "2") (pinfunction "2_2") (pintype "passive"))
    )
    (net (code "63") (name "Net-(LD5-AG)") (class "Default")
      (node (ref "LD5") (pin "AX") (pinfunction "AG_AX") (pintype "passive"))
      (node (ref "R9") (pin "1") (pinfunction "1_1") (pintype "passive"))
    )
    (net (code "64") (name "Net-(LD5-PadAR)") (class "Default")
      (node (ref "LD5") (pin "AR") (pinfunction "AR_AR") (pintype "passive"))
      (node (ref "R10") (pin "2") (pinfunction "2_2") (pintype "passive"))
    )
    (net (code "65") (name "Net-(LD6-AG)") (class "Default")
      (node (ref "LD6") (pin "AX") (pinfunction "AG_AX") (pintype "passive"))
      (node (ref "R11") (pin "1") (pinfunction "1_1") (pintype "passive"))
    )
    (net (code "66") (name "Net-(LD6-PadAR)") (class "Default")
      (node (ref "LD6") (pin "AR") (pinfunction "AR_AR") (pintype "passive"))
      (node (ref "R12") (pin "2") (pinfunction "2_2") (pintype "passive"))
    )
    (net (code "67") (name "Net-(LD7-AG)") (class "Default")
      (node (ref "LD7") (pin "AX") (pinfunction "AG_AX") (pintype "passive"))
      (node (ref "R13") (pin "1") (pinfunction "1_1") (pintype "passive"))
    )
    (net (code "68") (name "Net-(LD7-PadAR)") (class "Default")
      (node (ref "LD7") (pin "AR") (pinfunction "AR_AR") (pintype "passive"))
      (node (ref "R14") (pin "2") (pinfunction "2_2") (pintype "passive"))
    )
    (net (code "69") (name "Net-(LD8-AG)") (class "Default")
      (node (ref "LD8") (pin "AX") (pinfunction "AG_AX") (pintype "passive"))
      (node (ref "R15") (pin "1") (pinfunction "1_1") (pintype "passive"))
    )
    (net (code "70") (name "Net-(LD8-PadAR)") (class "Default")
      (node (ref "LD8") (pin "AR") (pinfunction "AR_AR") (pintype "passive"))
      (node (ref "R16") (pin "2") (pinfunction "2_2") (pintype "passive"))
    )
    (net (code "71") (name "Net-(LD9-AG)") (class "Default")
      (node (ref "LD9") (pin "AX") (pinfunction "AG_AX") (pintype "passive"))
      (node (ref "R17") (pin "1") (pinfunction "1_1") (pintype "passive"))
    )
    (net (code "72") (name "Net-(LD9-PadAR)") (class "Default")
      (node (ref "LD9") (pin "AR") (pinfunction "AR_AR") (pintype "passive"))
      (node (ref "R18") (pin "2") (pinfunction "2_2") (pintype "passive"))
    )
    (net (code "73") (name "Net-(LD10-AG)") (class "Default")
      (node (ref "LD10") (pin "AX") (pinfunction "AG_AX") (pintype "passive"))
      (node (ref "R19") (pin "1") (pinfunction "1_1") (pintype "passive"))
    )
    (net (code "74") (name "Net-(LD10-PadAR)") (class "Default")
      (node (ref "LD10") (pin "AR") (pinfunction "AR_AR") (pintype "passive"))
      (node (ref "R20") (pin "2") (pinfunction "2_2") (pintype "passive"))
    )
    (net (code "75") (name "Net-(LD11-AG)") (class "Default")
      (node (ref "LD11") (pin "AX") (pinfunction "AG_AX") (pintype "passive"))
      (node (ref "R21") (pin "1") (pinfunction "1_1") (pintype "passive"))
    )
    (net (code "76") (name "Net-(LD11-PadAR)") (class "Default")
      (node (ref "LD11") (pin "AR") (pinfunction "AR_AR") (pintype "passive"))
      (node (ref "R22") (pin "2") (pinfunction "2_2") (pintype "passive"))
    )
    (net (code "77") (name "Net-(Q1-B)") (class "Default")
      (node (ref "Q1") (pin "2") (pinfunction "B_2") (pintype "passive"))
      (node (ref "R29") (pin "1") (pinfunction "1_1") (pintype "passive"))
    )
    (net (code "78") (name "Net-(R23-Pad2)") (class "Default")
      (node (ref "R23") (pin "2") (pinfunction "2_2") (pintype "passive"))
      (node (ref "R29") (pin "2") (pinfunction "2_2") (pintype "passive"))
      (node (ref "U$3") (pin "E") (pinfunction "E_E") (pintype "passive"))
    )
    (net (code "79") (name "Net-(U$15-EN)") (class "Default")
      (node (ref "C14") (pin "2") (pinfunction "2_2") (pintype "passive"))
      (node (ref "R25") (pin "1") (pinfunction "1_1") (pintype "passive"))
      (node (ref "U$15") (pin "2") (pinfunction "EN_2") (pintype "bidirectional"))
    )
    (net (code "80") (name "Net-(U$15-IO15)") (class "Default")
      (node (ref "R27") (pin "2") (pinfunction "2_2") (pintype "passive"))
      (node (ref "U$15") (pin "6") (pinfunction "IO15_6") (pintype "bidirectional"))
    )
    (net (code "81") (name "Net-(U$15-~{RST})") (class "Default")
      (node (ref "R26") (pin "1") (pinfunction "1_1") (pintype "passive"))
      (node (ref "U$15") (pin "15") (pinfunction "~{RST}_15") (pintype "bidirectional"))
    )
    (net (code "82") (name "unconnected-(Q1-C-Pad3)") (class "Default")
      (node (ref "Q1") (pin "3") (pinfunction "C_3") (pintype "passive"))
    )
    (net (code "83") (name "unconnected-(SL1-Pad8)") (class "Default")
      (node (ref "SL1") (pin "8") (pinfunction "8_8") (pintype "passive"))
    )
    (net (code "84") (name "unconnected-(U$1-ACA0OUT{slash}ACA7{slash}ADCA7{slash}PA7-Pad2)") (class "Default")
      (node (ref "U$1") (pin "2") (pinfunction "ACA0OUT/ACA7/ADCA7/PA7_2") (pintype "bidirectional"))
    )
    (net (code "85") (name "unconnected-(U$1-ACA6{slash}ADCA6{slash}PA6-Pad1)") (class "Default")
      (node (ref "U$1") (pin "1") (pinfunction "ACA6/ADCA6/PA6_1") (pintype "bidirectional"))
    )
    (net (code "86") (name "unconnected-(U$1-ACB1{slash}ADCB1{slash}PB1-Pad6)") (class "Default")
      (node (ref "U$1") (pin "6") (pinfunction "ACB1/ADCB1/PB1_6") (pintype "bidirectional"))
    )
    (net (code "87") (name "unconnected-(U$1-AREFB{slash}ACB0{slash}ADCB0{slash}PB0-Pad5)") (class "Default")
      (node (ref "U$1") (pin "5") (pinfunction "AREFB/ACB0/ADCB0/PB0_5") (pintype "bidirectional"))
    )
    (net (code "88") (name "unconnected-(U$1-DACB0{slash}ACB2{slash}ADCB2{slash}PB2-Pad7)") (class "Default")
      (node (ref "U$1") (pin "7") (pinfunction "DACB0/ACB2/ADCB2/PB2_7") (pintype "bidirectional"))
    )
    (net (code "89") (name "unconnected-(U$1-DACB1{slash}ACB3{slash}ADCB3{slash}PB3-Pad8)") (class "Default")
      (node (ref "U$1") (pin "8") (pinfunction "DACB1/ACB3/ADCB3/PB3_8") (pintype "bidirectional"))
    )
    (net (code "90") (name "unconnected-(U$1-MISO{slash}RXD1{slash}OC0DLS{slash}PC6-Pad21)") (class "Default")
      (node (ref "U$1") (pin "21") (pinfunction "MISO/RXD1/OC0DLS/PC6_21") (pintype "bidirectional"))
    )
    (net (code "91") (name "unconnected-(U$1-MISO{slash}RXD1{slash}OC0DLS{slash}PE6-Pad41)") (class "Default")
      (node (ref "U$1") (pin "41") (pinfunction "MISO/RXD1/OC0DLS/PE6_41") (pintype "bidirectional"))
    )
    (net (code "92") (name "unconnected-(U$1-MISO{slash}RXD1{slash}PF6-Pad51)") (class "Default")
      (node (ref "U$1") (pin "51") (pinfunction "MISO/RXD1/PF6_51") (pintype "bidirectional"))
    )
    (net (code "93") (name "unconnected-(U$1-MOSI{slash}XCK1{slash}0C1B{slash}PF5-Pad50)") (class "Default")
      (node (ref "U$1") (pin "50") (pinfunction "MOSI/XCK1/0C1B/PF5_50") (pintype "bidirectional"))
    )
    (net (code "94") (name "unconnected-(U$1-PDI_DATA-Pad89)") (class "Default")
      (node (ref "U$1") (pin "89") (pinfunction "PDI_DATA_89") (pintype "bidirectional"))
    )
    (net (code "95") (name "unconnected-(U$1-PH0{slash}SDRAM-Pad55)") (class "Default")
      (node (ref "U$1") (pin "55") (pinfunction "PH0/SDRAM_55") (pintype "bidirectional"))
    )
    (net (code "96") (name "unconnected-(U$1-PH1{slash}SDRAM-Pad56)") (class "Default")
      (node (ref "U$1") (pin "56") (pinfunction "PH1/SDRAM_56") (pintype "bidirectional"))
    )
    (net (code "97") (name "unconnected-(U$1-PH3{slash}SDRAM-Pad58)") (class "Default")
      (node (ref "U$1") (pin "58") (pinfunction "PH3/SDRAM_58") (pintype "bidirectional"))
    )
    (net (code "98") (name "unconnected-(U$1-PH4{slash}SDRAM-Pad59)") (class "Default")
      (node (ref "U$1") (pin "59") (pinfunction "PH4/SDRAM_59") (pintype "bidirectional"))
    )
    (net (code "99") (name "unconnected-(U$1-PH5{slash}SDRAM-Pad60)") (class "Default")
      (node (ref "U$1") (pin "60") (pinfunction "PH5/SDRAM_60") (pintype "bidirectional"))
    )
    (net (code "100") (name "unconnected-(U$1-PH6{slash}SDRAM-Pad61)") (class "Default")
      (node (ref "U$1") (pin "61") (pinfunction "PH6/SDRAM_61") (pintype "bidirectional"))
    )
    (net (code "101") (name "unconnected-(U$1-PH7{slash}SDRAM-Pad62)") (class "Default")
      (node (ref "U$1") (pin "62") (pinfunction "PH7/SDRAM_62") (pintype "bidirectional"))
    )
    (net (code "102") (name "unconnected-(U$1-PJ6{slash}SDRAM-Pad71)") (class "Default")
      (node (ref "U$1") (pin "71") (pinfunction "PJ6/SDRAM_71") (pintype "bidirectional"))
    )
    (net (code "103") (name "unconnected-(U$1-PJ7{slash}SDRAM-Pad72)") (class "Default")
      (node (ref "U$1") (pin "72") (pinfunction "PJ7/SDRAM_72") (pintype "bidirectional"))
    )
    (net (code "104") (name "unconnected-(U$1-PK5{slash}SDRAM-Pad80)") (class "Default")
      (node (ref "U$1") (pin "80") (pinfunction "PK5/SDRAM_80") (pintype "bidirectional"))
    )
    (net (code "105") (name "unconnected-(U$1-PK7{slash}SDRAM-Pad82)") (class "Default")
      (node (ref "U$1") (pin "82") (pinfunction "PK7/SDRAM_82") (pintype "bidirectional"))
    )
    (net (code "106") (name "unconnected-(U$1-PQ0{slash}TOSC1-Pad85)") (class "Default")
      (node (ref "U$1") (pin "85") (pinfunction "PQ0/TOSC1_85") (pintype "bidirectional"))
    )
    (net (code "107") (name "unconnected-(U$1-PQ1{slash}TOSC2-Pad86)") (class "Default")
      (node (ref "U$1") (pin "86") (pinfunction "PQ1/TOSC2_86") (pintype "bidirectional"))
    )
    (net (code "108") (name "unconnected-(U$1-PQ2-Pad87)") (class "Default")
      (node (ref "U$1") (pin "87") (pinfunction "PQ2_87") (pintype "bidirectional"))
    )
    (net (code "109") (name "unconnected-(U$1-PQ3-Pad88)") (class "Default")
      (node (ref "U$1") (pin "88") (pinfunction "PQ3_88") (pintype "bidirectional"))
    )
    (net (code "110") (name "unconnected-(U$1-PR0{slash}XTAL2-Pad91)") (class "Default")
      (node (ref "U$1") (pin "91") (pinfunction "PR0/XTAL2_91") (pintype "bidirectional"))
    )
    (net (code "111") (name "unconnected-(U$1-PR1{slash}XTAL1-Pad92)") (class "Default")
      (node (ref "U$1") (pin "92") (pinfunction "PR1/XTAL1_92") (pintype "bidirectional"))
    )
    (net (code "112") (name "unconnected-(U$1-SCK{slash}TXD1{slash}OC0DHS{slash}PC7-Pad22)") (class "Default")
      (node (ref "U$1") (pin "22") (pinfunction "SCK/TXD1/OC0DHS/PC7_22") (pintype "bidirectional"))
    )
    (net (code "113") (name "unconnected-(U$1-SCK{slash}TXD1{slash}OC0DHS{slash}PE7-Pad42)") (class "Default")
      (node (ref "U$1") (pin "42") (pinfunction "SCK/TXD1/OC0DHS/PE7_42") (pintype "bidirectional"))
    )
    (net (code "114") (name "unconnected-(U$1-SCK{slash}TXD1{slash}PF7-Pad52)") (class "Default")
      (node (ref "U$1") (pin "52") (pinfunction "SCK/TXD1/PF7_52") (pintype "bidirectional"))
    )
    (net (code "115") (name "unconnected-(U$1-~{SS}{slash}0C1A{slash}PF4-Pad49)") (class "Default")
      (node (ref "U$1") (pin "49") (pinfunction "~{SS}/0C1A/PF4_49") (pintype "bidirectional"))
    )
    (net (code "116") (name "unconnected-(U$15-IO2-Pad7)") (class "Default")
      (node (ref "U$15") (pin "7") (pinfunction "IO2_7") (pintype "bidirectional"))
    )
    (net (code "117") (name "unconnected-(U$15-IO4-Pad10)") (class "Default")
      (node (ref "U$15") (pin "10") (pinfunction "IO4_10") (pintype "bidirectional"))
    )
    (net (code "118") (name "unconnected-(U$15-IO5-Pad14)") (class "Default")
      (node (ref "U$15") (pin "14") (pinfunction "IO5_14") (pintype "bidirectional"))
    )
    (net (code "119") (name "unconnected-(U$15-IO12-Pad4)") (class "Default")
      (node (ref "U$15") (pin "4") (pinfunction "IO12_4") (pintype "bidirectional"))
    )
    (net (code "120") (name "unconnected-(U$15-IO13-Pad5)") (class "Default")
      (node (ref "U$15") (pin "5") (pinfunction "IO13_5") (pintype "bidirectional"))
    )
    (net (code "121") (name "unconnected-(U$15-IO14-Pad3)") (class "Default")
      (node (ref "U$15") (pin "3") (pinfunction "IO14_3") (pintype "bidirectional"))
    )
    (net (code "122") (name "unconnected-(U$15-IO16-Pad17)") (class "Default")
      (node (ref "U$15") (pin "17") (pinfunction "IO16_17") (pintype "bidirectional"))
    )
    (net (code "123") (name "unconnected-(U$15-TOUT-Pad16)") (class "Default")
      (node (ref "U$15") (pin "16") (pinfunction "TOUT_16") (pintype "bidirectional"))
    )
  )
)
